# robot_arm.net
KiCad netlist of a schematic drawn in EAGLE
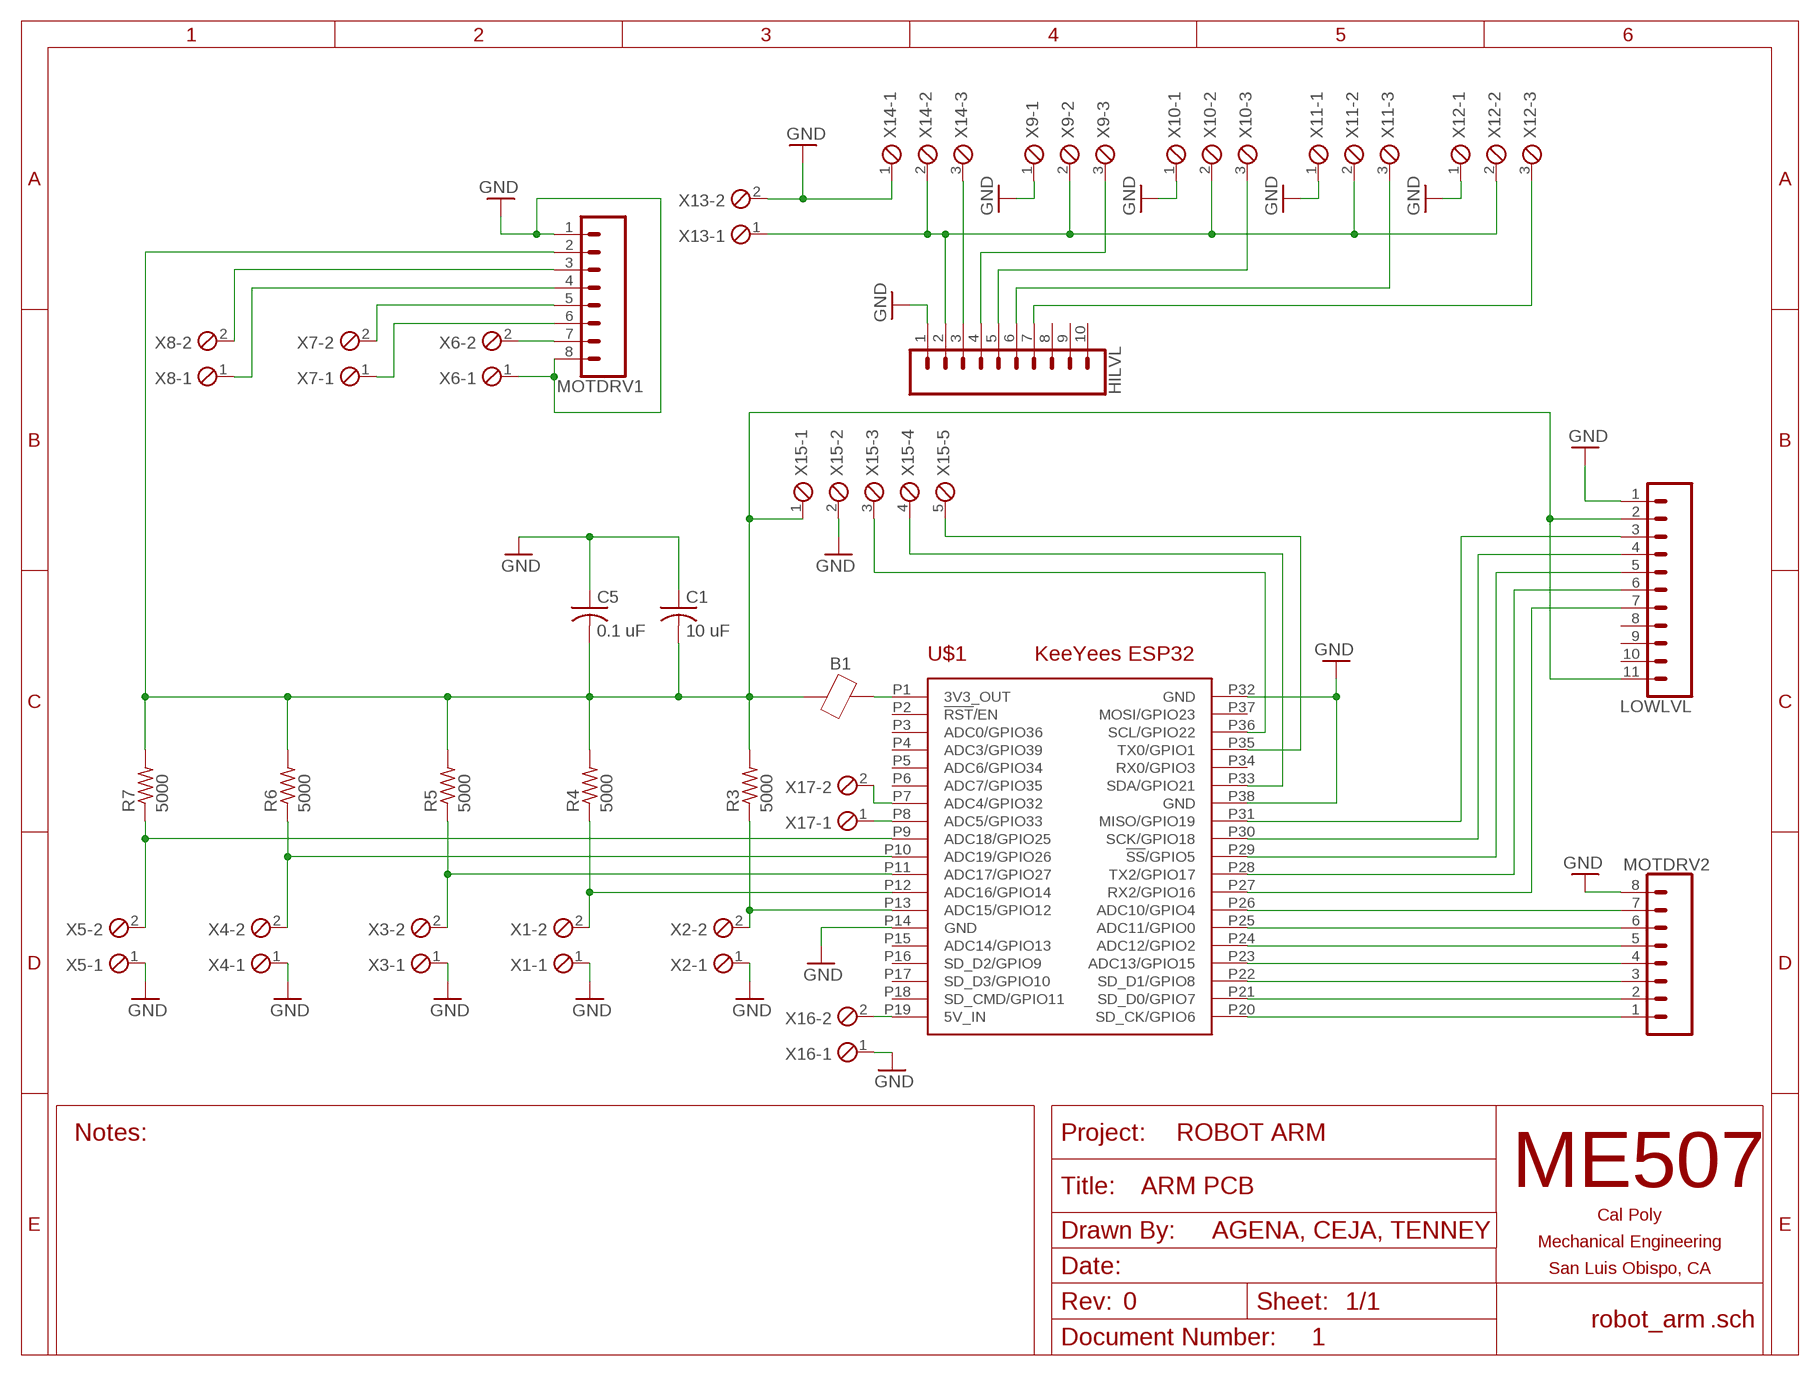
[diagram p0: schematic, sheet 1]

(export (version "E")
  (design (tool "Eeschema 10.0.6"))
  (components
    (comp (ref "B1")
      (value "BEAD0805")
      (footprint "eagle-import:0805")
      (libsource (lib "eagle-import") (part "BEAD0805"))
    )
    (comp (ref "C1")
      (value "10 uF")
      (footprint "eagle-import:C0805")
      (libsource (lib "eagle-import") (part "C-USC0805"))
    )
    (comp (ref "C5")
      (value "0.1 uF")
      (footprint "eagle-import:C0805")
      (libsource (lib "eagle-import") (part "C-USC0805"))
    )
    (comp (ref "HILVL")
      (value "CONN_10\"")
      (footprint "eagle-import:1X10")
      (libsource (lib "eagle-import") (part "CONN_10{dblquote}"))
    )
    (comp (ref "LOWLVL")
      (value "CONN_11")
      (footprint "eagle-import:1X11")
      (libsource (lib "eagle-import") (part "CONN_11"))
    )
    (comp (ref "MOTDRV1")
      (value "CONN_08\"")
      (footprint "eagle-import:1X08")
      (libsource (lib "eagle-import") (part "CONN_08{dblquote}"))
    )
    (comp (ref "MOTDRV2")
      (value "CONN_08\"")
      (footprint "eagle-import:1X08")
      (libsource (lib "eagle-import") (part "CONN_08{dblquote}"))
    )
    (comp (ref "R3")
      (value "5000")
      (footprint "eagle-import:R0805")
      (libsource (lib "eagle-import") (part "R-US_R0805"))
    )
    (comp (ref "R4")
      (value "5000")
      (footprint "eagle-import:R0805")
      (libsource (lib "eagle-import") (part "R-US_R0805"))
    )
    (comp (ref "R5")
      (value "5000")
      (footprint "eagle-import:R0805")
      (libsource (lib "eagle-import") (part "R-US_R0805"))
    )
    (comp (ref "R6")
      (value "5000")
      (footprint "eagle-import:R0805")
      (libsource (lib "eagle-import") (part "R-US_R0805"))
    )
    (comp (ref "R7")
      (value "5000")
      (footprint "eagle-import:R0805")
      (libsource (lib "eagle-import") (part "R-US_R0805"))
    )
    (comp (ref "U$1")
      (value "KEEYEES_ESP32EXT")
      (footprint "eagle-import:KEEYEES_ESP32_EXTENDED")
      (libsource (lib "eagle-import") (part "KEEYEES_ESP32EXT"))
    )
    (comp (ref "X1")
      (value "SCREWTERM_2P_254")
      (footprint "eagle-import:2POL254")
      (libsource (lib "eagle-import") (part "SCREWTERM_2P_254"))
    )
    (comp (ref "X2")
      (value "SCREWTERM_2P_254")
      (footprint "eagle-import:2POL254")
      (libsource (lib "eagle-import") (part "SCREWTERM_2P_254"))
    )
    (comp (ref "X3")
      (value "SCREWTERM_2P_254")
      (footprint "eagle-import:2POL254")
      (libsource (lib "eagle-import") (part "SCREWTERM_2P_254"))
    )
    (comp (ref "X4")
      (value "SCREWTERM_2P_254")
      (footprint "eagle-import:2POL254")
      (libsource (lib "eagle-import") (part "SCREWTERM_2P_254"))
    )
    (comp (ref "X5")
      (value "SCREWTERM_2P_254")
      (footprint "eagle-import:2POL254")
      (libsource (lib "eagle-import") (part "SCREWTERM_2P_254"))
    )
    (comp (ref "X6")
      (value "SCREWTERM_2P_254")
      (footprint "eagle-import:2POL254")
      (libsource (lib "eagle-import") (part "SCREWTERM_2P_254"))
    )
    (comp (ref "X7")
      (value "SCREWTERM_2P_254")
      (footprint "eagle-import:2POL254")
      (libsource (lib "eagle-import") (part "SCREWTERM_2P_254"))
    )
    (comp (ref "X8")
      (value "SCREWTERM_2P_254")
      (footprint "eagle-import:2POL254")
      (libsource (lib "eagle-import") (part "SCREWTERM_2P_254"))
    )
    (comp (ref "X9")
      (value "SCREWTERM_3P_254")
      (footprint "eagle-import:3POL254")
      (libsource (lib "eagle-import") (part "SCREWTERM_3P_254"))
    )
    (comp (ref "X10")
      (value "SCREWTERM_3P_254")
      (footprint "eagle-import:3POL254")
      (libsource (lib "eagle-import") (part "SCREWTERM_3P_254"))
    )
    (comp (ref "X11")
      (value "SCREWTERM_3P_254")
      (footprint "eagle-import:3POL254")
      (libsource (lib "eagle-import") (part "SCREWTERM_3P_254"))
    )
    (comp (ref "X12")
      (value "SCREWTERM_3P_254")
      (footprint "eagle-import:3POL254")
      (libsource (lib "eagle-import") (part "SCREWTERM_3P_254"))
    )
    (comp (ref "X13")
      (value "SCREWTERM_2P_254")
      (footprint "eagle-import:2POL254")
      (libsource (lib "eagle-import") (part "SCREWTERM_2P_254"))
    )
    (comp (ref "X14")
      (value "SCREWTERM_3P_254")
      (footprint "eagle-import:3POL254")
      (libsource (lib "eagle-import") (part "SCREWTERM_3P_254"))
    )
    (comp (ref "X15")
      (value "SCREWTERM_5P_254")
      (footprint "eagle-import:5POL254")
      (libsource (lib "eagle-import") (part "SCREWTERM_5P_254"))
    )
    (comp (ref "X16")
      (value "SCREWTERM_2P_254")
      (footprint "eagle-import:2POL254")
      (libsource (lib "eagle-import") (part "SCREWTERM_2P_254"))
    )
    (comp (ref "X17")
      (value "SCREWTERM_2P_254")
      (footprint "eagle-import:2POL254")
      (libsource (lib "eagle-import") (part "SCREWTERM_2P_254"))
    )
  )
  (nets
    (net (code "1") (name "GND") (class "Default")
      (node (ref "C1") (pin "1") (pinfunction "1_1") (pintype "passive"))
      (node (ref "C5") (pin "1") (pinfunction "1_1") (pintype "passive"))
      (node (ref "HILVL") (pin "1") (pinfunction "1_1") (pintype "passive"))
      (node (ref "LOWLVL") (pin "1") (pinfunction "1_1") (pintype "passive"))
      (node (ref "MOTDRV1") (pin "1") (pinfunction "1_1") (pintype "passive"))
      (node (ref "MOTDRV1") (pin "8") (pinfunction "8_8") (pintype "passive"))
      (node (ref "MOTDRV2") (pin "8") (pinfunction "8_8") (pintype "passive"))
      (node (ref "U$1") (pin "P14") (pinfunction "GND_P14") (pintype "power_in"))
      (node (ref "U$1") (pin "P32") (pinfunction "GND_P32") (pintype "power_in"))
      (node (ref "U$1") (pin "P38") (pinfunction "GND_P38") (pintype "power_in"))
      (node (ref "X1") (pin "1") (pinfunction "1_1") (pintype "passive"))
      (node (ref "X10") (pin "1") (pinfunction "1_1") (pintype "passive"))
      (node (ref "X11") (pin "1") (pinfunction "1_1") (pintype "passive"))
      (node (ref "X12") (pin "1") (pinfunction "1_1") (pintype "passive"))
      (node (ref "X13") (pin "2") (pinfunction "1_2") (pintype "passive"))
      (node (ref "X14") (pin "1") (pinfunction "1_1") (pintype "passive"))
      (node (ref "X15") (pin "2") (pinfunction "1_2") (pintype "passive"))
      (node (ref "X16") (pin "1") (pinfunction "1_1") (pintype "passive"))
      (node (ref "X2") (pin "1") (pinfunction "1_1") (pintype "passive"))
      (node (ref "X3") (pin "1") (pinfunction "1_1") (pintype "passive"))
      (node (ref "X4") (pin "1") (pinfunction "1_1") (pintype "passive"))
      (node (ref "X5") (pin "1") (pinfunction "1_1") (pintype "passive"))
      (node (ref "X6") (pin "1") (pinfunction "1_1") (pintype "passive"))
      (node (ref "X9") (pin "1") (pinfunction "1_1") (pintype "passive"))
    )
    (net (code "2") (name "Net-(B1-Pad1)") (class "Default")
      (node (ref "B1") (pin "1") (pinfunction "1_1") (pintype "bidirectional"))
      (node (ref "C1") (pin "2") (pinfunction "2_2") (pintype "passive"))
      (node (ref "C5") (pin "2") (pinfunction "2_2") (pintype "passive"))
      (node (ref "LOWLVL") (pin "11") (pinfunction "11_11") (pintype "passive"))
      (node (ref "LOWLVL") (pin "2") (pinfunction "2_2") (pintype "passive"))
      (node (ref "MOTDRV1") (pin "2") (pinfunction "2_2") (pintype "passive"))
      (node (ref "R3") (pin "2") (pinfunction "2_2") (pintype "passive"))
      (node (ref "R4") (pin "2") (pinfunction "2_2") (pintype "passive"))
      (node (ref "R5") (pin "2") (pinfunction "2_2") (pintype "passive"))
      (node (ref "R6") (pin "2") (pinfunction "2_2") (pintype "passive"))
      (node (ref "R7") (pin "2") (pinfunction "2_2") (pintype "passive"))
      (node (ref "X15") (pin "1") (pinfunction "1_1") (pintype "passive"))
    )
    (net (code "3") (name "Net-(MOTDRV1-Pad4)") (class "Default")
      (node (ref "MOTDRV1") (pin "4") (pinfunction "4_4") (pintype "passive"))
      (node (ref "X8") (pin "1") (pinfunction "1_1") (pintype "passive"))
    )
    (net (code "4") (name "Net-(MOTDRV1-Pad6)") (class "Default")
      (node (ref "MOTDRV1") (pin "6") (pinfunction "6_6") (pintype "passive"))
      (node (ref "X7") (pin "1") (pinfunction "1_1") (pintype "passive"))
    )
    (net (code "5") (name "Net-(U$1-3V3_OUT)") (class "Default")
      (node (ref "B1") (pin "2") (pinfunction "2_2") (pintype "bidirectional"))
      (node (ref "U$1") (pin "P1") (pinfunction "3V3_OUT_P1") (pintype "power_in"))
    )
    (net (code "6") (name "Net-(U$1-5V_IN)") (class "Default")
      (node (ref "U$1") (pin "P19") (pinfunction "5V_IN_P19") (pintype "power_in"))
      (node (ref "X16") (pin "2") (pinfunction "1_2") (pintype "passive"))
    )
    (net (code "7") (name "Net-(U$1-ADC4{slash}GPIO32)") (class "Default")
      (node (ref "U$1") (pin "P7") (pinfunction "ADC4/GPIO32_P7") (pintype "bidirectional"))
      (node (ref "X17") (pin "2") (pinfunction "1_2") (pintype "passive"))
    )
    (net (code "8") (name "Net-(U$1-ADC5{slash}GPIO33)") (class "Default")
      (node (ref "U$1") (pin "P8") (pinfunction "ADC5/GPIO33_P8") (pintype "bidirectional"))
      (node (ref "X17") (pin "1") (pinfunction "1_1") (pintype "passive"))
    )
    (net (code "9") (name "Net-(U$1-ADC10{slash}GPIO4)") (class "Default")
      (node (ref "MOTDRV2") (pin "7") (pinfunction "7_7") (pintype "passive"))
      (node (ref "U$1") (pin "P26") (pinfunction "ADC10/GPIO4_P26") (pintype "bidirectional"))
    )
    (net (code "10") (name "Net-(U$1-ADC11{slash}GPIO0)") (class "Default")
      (node (ref "MOTDRV2") (pin "6") (pinfunction "6_6") (pintype "passive"))
      (node (ref "U$1") (pin "P25") (pinfunction "ADC11/GPIO0_P25") (pintype "bidirectional"))
    )
    (net (code "11") (name "Net-(U$1-ADC12{slash}GPIO2)") (class "Default")
      (node (ref "MOTDRV2") (pin "5") (pinfunction "5_5") (pintype "passive"))
      (node (ref "U$1") (pin "P24") (pinfunction "ADC12/GPIO2_P24") (pintype "bidirectional"))
    )
    (net (code "12") (name "Net-(U$1-ADC13{slash}GPIO15)") (class "Default")
      (node (ref "MOTDRV2") (pin "4") (pinfunction "4_4") (pintype "passive"))
      (node (ref "U$1") (pin "P23") (pinfunction "ADC13/GPIO15_P23") (pintype "bidirectional"))
    )
    (net (code "13") (name "Net-(U$1-ADC15{slash}GPIO12)") (class "Default")
      (node (ref "R3") (pin "1") (pinfunction "1_1") (pintype "passive"))
      (node (ref "U$1") (pin "P13") (pinfunction "ADC15/GPIO12_P13") (pintype "bidirectional"))
      (node (ref "X2") (pin "2") (pinfunction "1_2") (pintype "passive"))
    )
    (net (code "14") (name "Net-(U$1-ADC16{slash}GPIO14)") (class "Default")
      (node (ref "R4") (pin "1") (pinfunction "1_1") (pintype "passive"))
      (node (ref "U$1") (pin "P12") (pinfunction "ADC16/GPIO14_P12") (pintype "bidirectional"))
      (node (ref "X1") (pin "2") (pinfunction "1_2") (pintype "passive"))
    )
    (net (code "15") (name "Net-(U$1-ADC17{slash}GPIO27)") (class "Default")
      (node (ref "R5") (pin "1") (pinfunction "1_1") (pintype "passive"))
      (node (ref "U$1") (pin "P11") (pinfunction "ADC17/GPIO27_P11") (pintype "bidirectional"))
      (node (ref "X3") (pin "2") (pinfunction "1_2") (pintype "passive"))
    )
    (net (code "16") (name "Net-(U$1-ADC18{slash}GPIO25)") (class "Default")
      (node (ref "R7") (pin "1") (pinfunction "1_1") (pintype "passive"))
      (node (ref "U$1") (pin "P9") (pinfunction "ADC18/GPIO25_P9") (pintype "bidirectional"))
      (node (ref "X5") (pin "2") (pinfunction "1_2") (pintype "passive"))
    )
    (net (code "17") (name "Net-(U$1-ADC19{slash}GPIO26)") (class "Default")
      (node (ref "R6") (pin "1") (pinfunction "1_1") (pintype "passive"))
      (node (ref "U$1") (pin "P10") (pinfunction "ADC19/GPIO26_P10") (pintype "bidirectional"))
      (node (ref "X4") (pin "2") (pinfunction "1_2") (pintype "passive"))
    )
    (net (code "18") (name "Net-(U$1-MISO{slash}GPIO19)") (class "Default")
      (node (ref "LOWLVL") (pin "3") (pinfunction "3_3") (pintype "passive"))
      (node (ref "U$1") (pin "P31") (pinfunction "MISO/GPIO19_P31") (pintype "bidirectional"))
    )
    (net (code "19") (name "Net-(U$1-RX2{slash}GPIO16)") (class "Default")
      (node (ref "LOWLVL") (pin "7") (pinfunction "7_7") (pintype "passive"))
      (node (ref "U$1") (pin "P27") (pinfunction "RX2/GPIO16_P27") (pintype "bidirectional"))
    )
    (net (code "20") (name "Net-(U$1-SCK{slash}GPIO18)") (class "Default")
      (node (ref "LOWLVL") (pin "4") (pinfunction "4_4") (pintype "passive"))
      (node (ref "U$1") (pin "P30") (pinfunction "SCK/GPIO18_P30") (pintype "bidirectional"))
    )
    (net (code "21") (name "Net-(U$1-SCL{slash}GPIO22)") (class "Default")
      (node (ref "U$1") (pin "P36") (pinfunction "SCL/GPIO22_P36") (pintype "bidirectional"))
      (node (ref "X15") (pin "3") (pinfunction "1_3") (pintype "passive"))
    )
    (net (code "22") (name "Net-(U$1-SDA{slash}GPIO21)") (class "Default")
      (node (ref "U$1") (pin "P33") (pinfunction "SDA/GPIO21_P33") (pintype "bidirectional"))
      (node (ref "X15") (pin "4") (pinfunction "1_4") (pintype "passive"))
    )
    (net (code "23") (name "Net-(U$1-SD_CK{slash}GPIO6)") (class "Default")
      (node (ref "MOTDRV2") (pin "1") (pinfunction "1_1") (pintype "passive"))
      (node (ref "U$1") (pin "P20") (pinfunction "SD_CK/GPIO6_P20") (pintype "bidirectional"))
    )
    (net (code "24") (name "Net-(U$1-SD_D0{slash}GPIO7)") (class "Default")
      (node (ref "MOTDRV2") (pin "2") (pinfunction "2_2") (pintype "passive"))
      (node (ref "U$1") (pin "P21") (pinfunction "SD_D0/GPIO7_P21") (pintype "bidirectional"))
    )
    (net (code "25") (name "Net-(U$1-SD_D1{slash}GPIO8)") (class "Default")
      (node (ref "MOTDRV2") (pin "3") (pinfunction "3_3") (pintype "passive"))
      (node (ref "U$1") (pin "P22") (pinfunction "SD_D1/GPIO8_P22") (pintype "bidirectional"))
    )
    (net (code "26") (name "Net-(U$1-TX0{slash}GPIO1)") (class "Default")
      (node (ref "U$1") (pin "P35") (pinfunction "TX0/GPIO1_P35") (pintype "bidirectional"))
      (node (ref "X15") (pin "5") (pinfunction "1_5") (pintype "passive"))
    )
    (net (code "27") (name "Net-(U$1-TX2{slash}GPIO17)") (class "Default")
      (node (ref "LOWLVL") (pin "6") (pinfunction "6_6") (pintype "passive"))
      (node (ref "U$1") (pin "P28") (pinfunction "TX2/GPIO17_P28") (pintype "bidirectional"))
    )
    (net (code "28") (name "Net-(U$1-~{SS}{slash}GPIO5)") (class "Default")
      (node (ref "LOWLVL") (pin "5") (pinfunction "5_5") (pintype "passive"))
      (node (ref "U$1") (pin "P29") (pinfunction "~{SS}/GPIO5_P29") (pintype "bidirectional"))
    )
    (net (code "29") (name "Net-(X6B-1)") (class "Default")
      (node (ref "MOTDRV1") (pin "7") (pinfunction "7_7") (pintype "passive"))
      (node (ref "X6") (pin "2") (pinfunction "1_2") (pintype "passive"))
    )
    (net (code "30") (name "Net-(X7B-1)") (class "Default")
      (node (ref "MOTDRV1") (pin "5") (pinfunction "5_5") (pintype "passive"))
      (node (ref "X7") (pin "2") (pinfunction "1_2") (pintype "passive"))
    )
    (net (code "31") (name "Net-(X8B-1)") (class "Default")
      (node (ref "MOTDRV1") (pin "3") (pinfunction "3_3") (pintype "passive"))
      (node (ref "X8") (pin "2") (pinfunction "1_2") (pintype "passive"))
    )
    (net (code "32") (name "Net-(X9C-1)") (class "Default")
      (node (ref "HILVL") (pin "4") (pinfunction "4_4") (pintype "passive"))
      (node (ref "X9") (pin "3") (pinfunction "1_3") (pintype "passive"))
    )
    (net (code "33") (name "Net-(X10B-1)") (class "Default")
      (node (ref "HILVL") (pin "2") (pinfunction "2_2") (pintype "passive"))
      (node (ref "X10") (pin "2") (pinfunction "1_2") (pintype "passive"))
      (node (ref "X11") (pin "2") (pinfunction "1_2") (pintype "passive"))
      (node (ref "X12") (pin "2") (pinfunction "1_2") (pintype "passive"))
      (node (ref "X13") (pin "1") (pinfunction "1_1") (pintype "passive"))
      (node (ref "X14") (pin "2") (pinfunction "1_2") (pintype "passive"))
      (node (ref "X9") (pin "2") (pinfunction "1_2") (pintype "passive"))
    )
    (net (code "34") (name "Net-(X10C-1)") (class "Default")
      (node (ref "HILVL") (pin "5") (pinfunction "5_5") (pintype "passive"))
      (node (ref "X10") (pin "3") (pinfunction "1_3") (pintype "passive"))
    )
    (net (code "35") (name "Net-(X11C-1)") (class "Default")
      (node (ref "HILVL") (pin "6") (pinfunction "6_6") (pintype "passive"))
      (node (ref "X11") (pin "3") (pinfunction "1_3") (pintype "passive"))
    )
    (net (code "36") (name "Net-(X12C-1)") (class "Default")
      (node (ref "HILVL") (pin "7") (pinfunction "7_7") (pintype "passive"))
      (node (ref "X12") (pin "3") (pinfunction "1_3") (pintype "passive"))
    )
    (net (code "37") (name "Net-(X14C-1)") (class "Default")
      (node (ref "HILVL") (pin "3") (pinfunction "3_3") (pintype "passive"))
      (node (ref "X14") (pin "3") (pinfunction "1_3") (pintype "passive"))
    )
    (net (code "38") (name "unconnected-(HILVL-Pad8)") (class "Default")
      (node (ref "HILVL") (pin "8") (pinfunction "8_8") (pintype "passive"))
    )
    (net (code "39") (name "unconnected-(HILVL-Pad9)") (class "Default")
      (node (ref "HILVL") (pin "9") (pinfunction "9_9") (pintype "passive"))
    )
    (net (code "40") (name "unconnected-(HILVL-Pad10)") (class "Default")
      (node (ref "HILVL") (pin "10") (pinfunction "10_10") (pintype "passive"))
    )
    (net (code "41") (name "unconnected-(LOWLVL-Pad8)") (class "Default")
      (node (ref "LOWLVL") (pin "8") (pinfunction "8_8") (pintype "passive"))
    )
    (net (code "42") (name "unconnected-(LOWLVL-Pad9)") (class "Default")
      (node (ref "LOWLVL") (pin "9") (pinfunction "9_9") (pintype "passive"))
    )
    (net (code "43") (name "unconnected-(LOWLVL-Pad10)") (class "Default")
      (node (ref "LOWLVL") (pin "10") (pinfunction "10_10") (pintype "passive"))
    )
    (net (code "44") (name "unconnected-(U$1-ADC0{slash}GPIO36-PadP3)") (class "Default")
      (node (ref "U$1") (pin "P3") (pinfunction "ADC0/GPIO36_P3") (pintype "bidirectional"))
    )
    (net (code "45") (name "unconnected-(U$1-ADC3{slash}GPIO39-PadP4)") (class "Default")
      (node (ref "U$1") (pin "P4") (pinfunction "ADC3/GPIO39_P4") (pintype "bidirectional"))
    )
    (net (code "46") (name "unconnected-(U$1-ADC6{slash}GPIO34-PadP5)") (class "Default")
      (node (ref "U$1") (pin "P5") (pinfunction "ADC6/GPIO34_P5") (pintype "bidirectional"))
    )
    (net (code "47") (name "unconnected-(U$1-ADC7{slash}GPIO35-PadP6)") (class "Default")
      (node (ref "U$1") (pin "P6") (pinfunction "ADC7/GPIO35_P6") (pintype "bidirectional"))
    )
    (net (code "48") (name "unconnected-(U$1-ADC14{slash}GPIO13-PadP15)") (class "Default")
      (node (ref "U$1") (pin "P15") (pinfunction "ADC14/GPIO13_P15") (pintype "bidirectional"))
    )
    (net (code "49") (name "unconnected-(U$1-MOSI{slash}GPIO23-PadP37)") (class "Default")
      (node (ref "U$1") (pin "P37") (pinfunction "MOSI/GPIO23_P37") (pintype "bidirectional"))
    )
    (net (code "50") (name "unconnected-(U$1-RX0{slash}GPIO3-PadP34)") (class "Default")
      (node (ref "U$1") (pin "P34") (pinfunction "RX0/GPIO3_P34") (pintype "bidirectional"))
    )
    (net (code "51") (name "unconnected-(U$1-SD_CMD{slash}GPIO11-PadP18)") (class "Default")
      (node (ref "U$1") (pin "P18") (pinfunction "SD_CMD/GPIO11_P18") (pintype "bidirectional"))
    )
    (net (code "52") (name "unconnected-(U$1-SD_D2{slash}GPIO9-PadP16)") (class "Default")
      (node (ref "U$1") (pin "P16") (pinfunction "SD_D2/GPIO9_P16") (pintype "bidirectional"))
    )
    (net (code "53") (name "unconnected-(U$1-SD_D3{slash}GPIO10-PadP17)") (class "Default")
      (node (ref "U$1") (pin "P17") (pinfunction "SD_D3/GPIO10_P17") (pintype "bidirectional"))
    )
    (net (code "54") (name "unconnected-(U$1-~{RST}{slash}EN-PadP2)") (class "Default")
      (node (ref "U$1") (pin "P2") (pinfunction "~{RST}/EN_P2") (pintype "input"))
    )
  )
)
